# OSSI-1_LED_Controller_1.net
KiCad netlist of a schematic drawn in Altium Designer
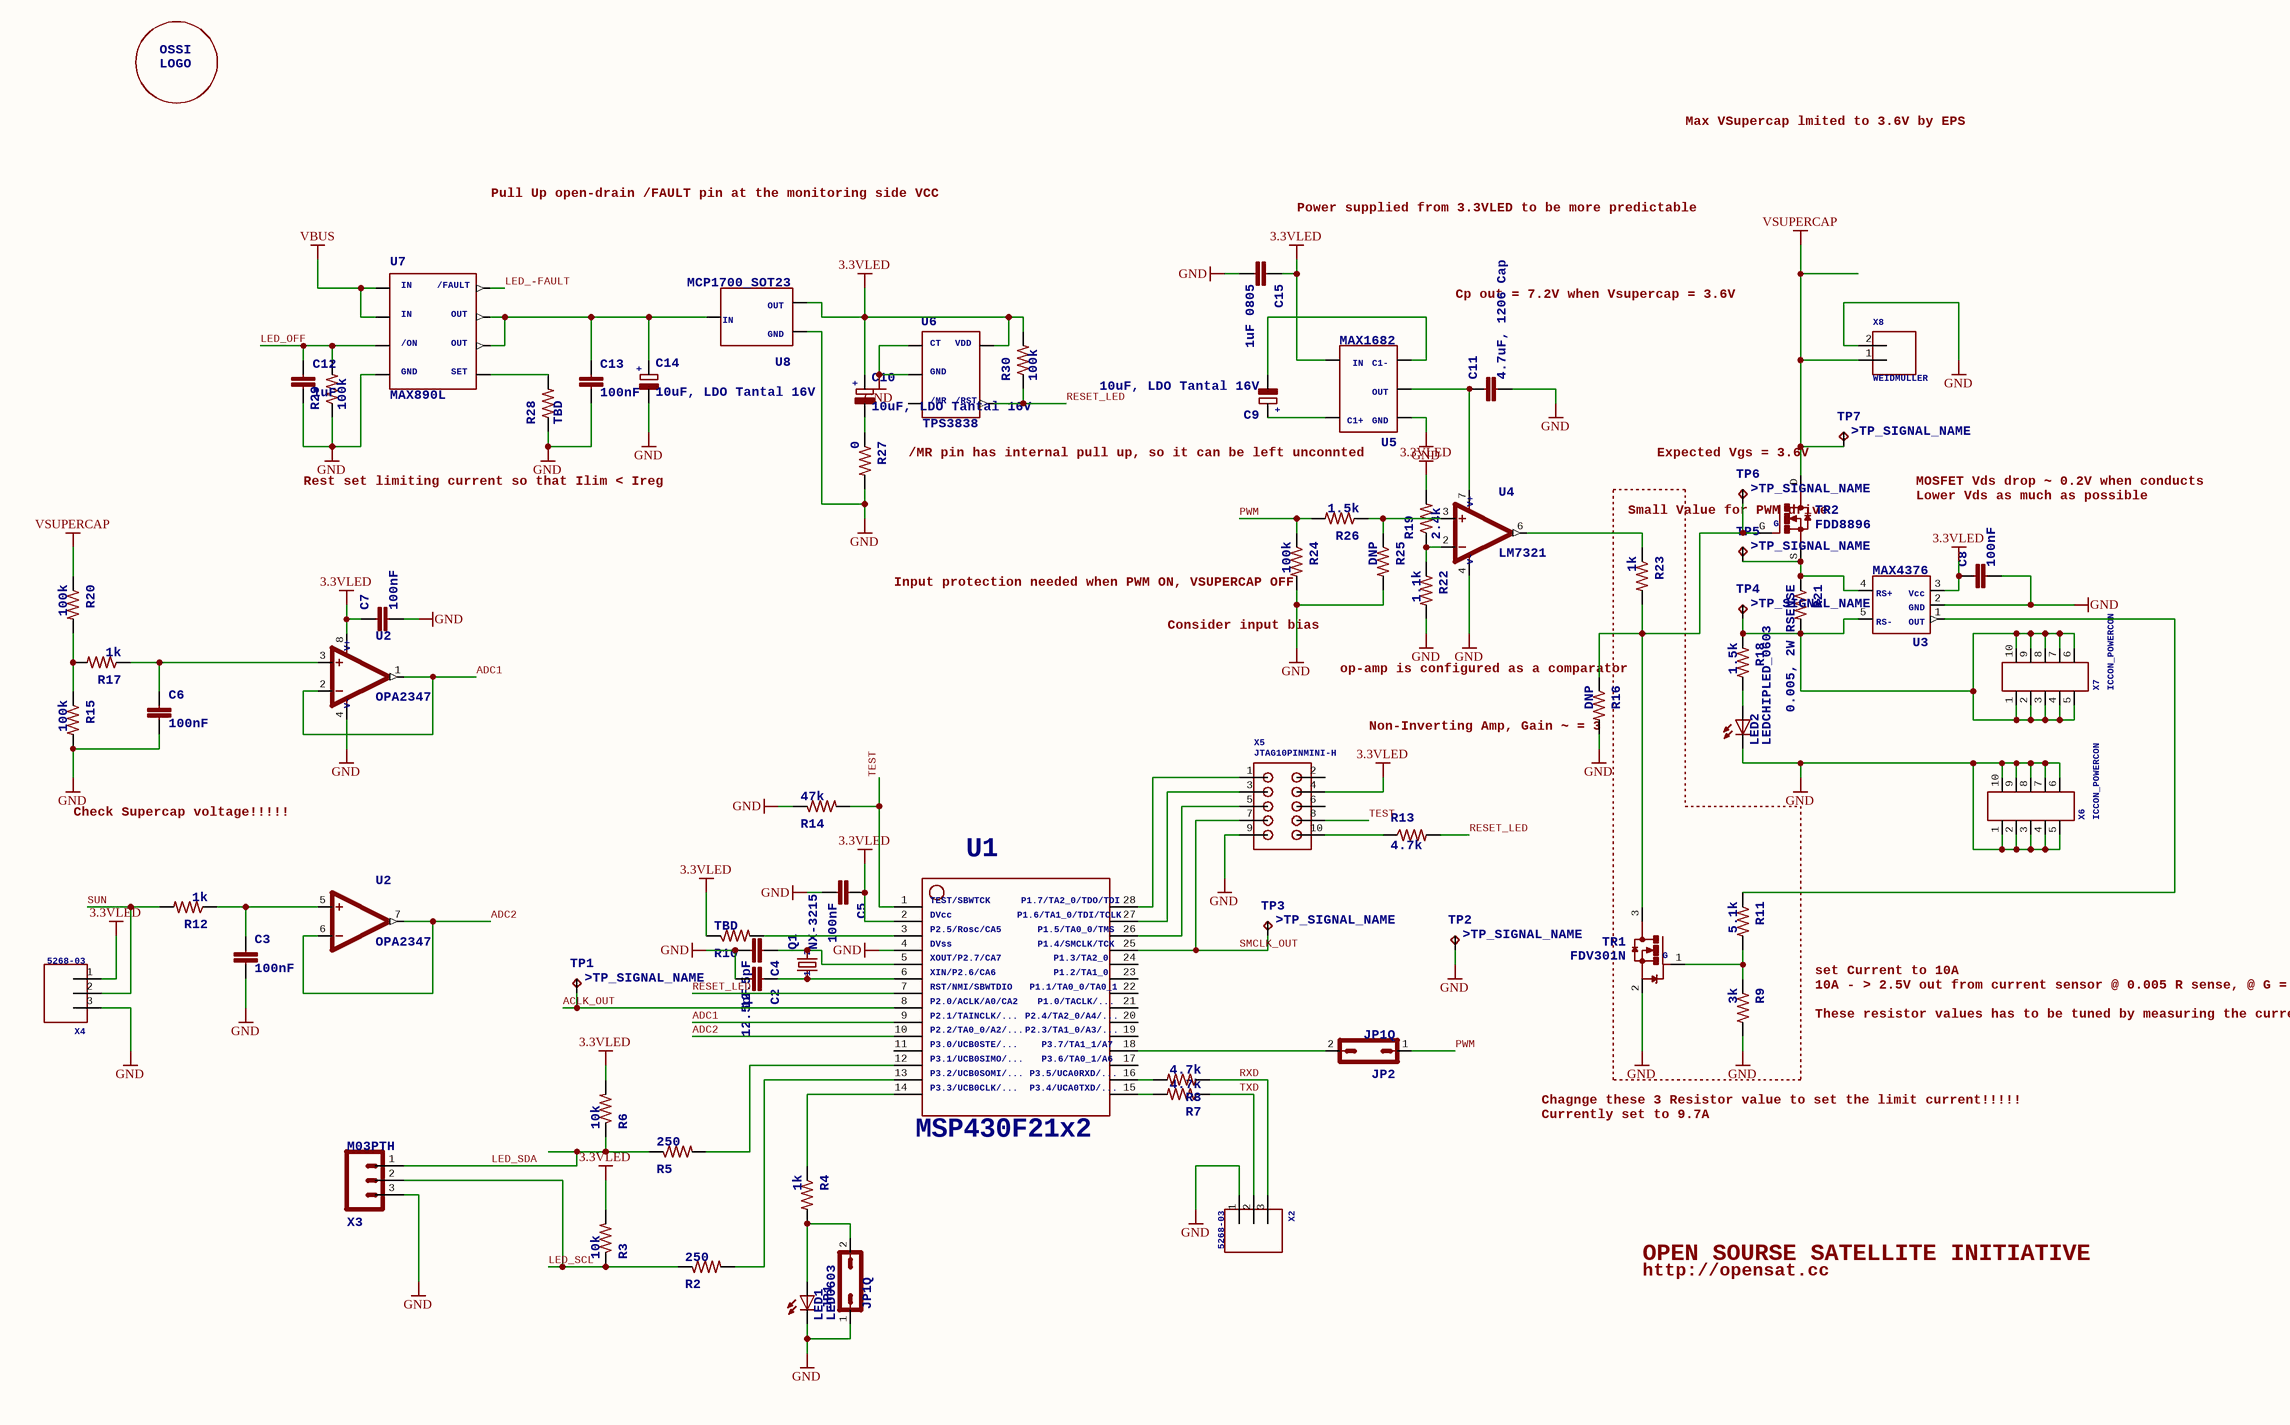
[diagram p0: OSSI-1 LED Controller_1.SchDoc]

(export (version "E")
  (design (tool "Eeschema 10.0.6"))
  (components
    (comp (ref "C2")
      (value "12.5pF")
      (footprint "C0603(1608)")
      (fields (field (name ">NAME") "C2") (field (name ">VALUE") "12.5pF"))
      (libsource (lib "") (part "C0603(1608)_2"))
    )
    (comp (ref "C3")
      (value "100nF")
      (footprint "C0603(1608)")
      (fields (field (name ">NAME") "C3") (field (name ">VALUE") "100nF"))
      (libsource (lib "OSSI") (part "C0603(1608)"))
    )
    (comp (ref "C4")
      (value "12.5pF")
      (footprint "C0603(1608)")
      (fields (field (name ">NAME") "C4") (field (name ">VALUE") "12.5pF"))
      (libsource (lib "") (part "C0603(1608)_2"))
    )
    (comp (ref "C5")
      (value "100nF")
      (footprint "C0603(1608)")
      (fields (field (name ">NAME") "C5") (field (name ">VALUE") "100nF"))
      (libsource (lib "") (part "C0603(1608)_2"))
    )
    (comp (ref "C6")
      (value "100nF")
      (footprint "C0603(1608)")
      (fields (field (name ">NAME") "C6") (field (name ">VALUE") "100nF"))
      (libsource (lib "OSSI") (part "C0603(1608)"))
    )
    (comp (ref "C7")
      (value "100nF")
      (footprint "C0603(1608)")
      (fields (field (name ">NAME") "C7") (field (name ">VALUE") "100nF"))
      (libsource (lib "") (part "C0603(1608)_1"))
    )
    (comp (ref "C8")
      (value "100nF")
      (footprint "C0603(1608)")
      (fields (field (name ">NAME") "C8") (field (name ">VALUE") "100nF"))
      (libsource (lib "") (part "C0603(1608)_1"))
    )
    (comp (ref "C9")
      (value "10uF, LDO Tantal 16V")
      (footprint "C1206(3216)-A")
      (fields
        (field (name ">NAME") "C9")
        (field (name "+") "+")
        (field (name ">VALUE") "10uF, LDO Tantal 16V")
      )
      (libsource (lib "OSSI") (part "C-TANTAL-A"))
    )
    (comp (ref "C10")
      (value "10uF, LDO Tantal 16V")
      (footprint "C1206(3216)-A")
      (fields
        (field (name ">NAME") "C10")
        (field (name "+") "+")
        (field (name ">VALUE") "10uF, LDO Tantal 16V")
      )
      (libsource (lib "") (part "C-TANTAL-A_1"))
    )
    (comp (ref "C11")
      (value "4.7uF, 1206 Cap")
      (footprint "C1206-GCM31")
      (fields (field (name ">NAME") "C11") (field (name ">VALUE") "4.7uF, 1206 Cap"))
      (libsource (lib "OSSI") (part "C1206(3216)-GCM31"))
    )
    (comp (ref "C12")
      (value "1uF")
      (footprint "C0603(1608)")
      (fields (field (name ">NAME") "C12") (field (name ">VALUE") "1uF"))
      (libsource (lib "OSSI") (part "C0603(1608)"))
    )
    (comp (ref "C13")
      (value "100nF")
      (footprint "C0603(1608)")
      (fields (field (name ">NAME") "C13") (field (name ">VALUE") "100nF"))
      (libsource (lib "OSSI") (part "C0603(1608)"))
    )
    (comp (ref "C14")
      (value "10uF, LDO Tantal 16V")
      (footprint "C1206(3216)-A")
      (fields
        (field (name ">NAME") "C14")
        (field (name "+") "+")
        (field (name ">VALUE") "10uF, LDO Tantal 16V")
      )
      (libsource (lib "") (part "C-TANTAL-A_1"))
    )
    (comp (ref "C15")
      (value "1uF 0805")
      (footprint "C0805(2012)")
      (fields (field (name ">NAME") "C15") (field (name ">VALUE") "1uF 0805"))
      (libsource (lib "OSSI") (part "C0805(2012)"))
    )
    (comp (ref "JP1")
      (value "JP1Q")
      (footprint "JP1")
      (description "<b>JUMPER</b>")
      (fields (field (name ">NAME") "JP1") (field (name ">VALUE") "JP1Q"))
      (libsource (lib "OSSI") (part "JP1Q"))
    )
    (comp (ref "JP2")
      (value "JP1Q")
      (footprint "JP1")
      (description "<b>JUMPER</b>")
      (fields (field (name ">NAME") "JP2") (field (name ">VALUE") "JP1Q"))
      (libsource (lib "OSSI") (part "JP1Q"))
    )
    (comp (ref "LED1")
      (value "LED0603")
      (footprint "LED-0603")
      (fields (field (name ">NAME") "LED1") (field (name ">VALUE") "LED0603"))
      (libsource (lib "SparkFun") (part "LED0603"))
    )
    (comp (ref "LED2")
      (value "LEDCHIPLED_0603")
      (footprint "CHIPLED_0603")
      (fields (field (name ">NAME") "LED2") (field (name ">VALUE") "LEDCHIPLED_0603"))
      (libsource (lib "led") (part "LEDCHIPLED_0603"))
    )
    (comp (ref "Q1")
      (value "NX-3215")
      (footprint "NX-3215")
      (fields
        (field (name ">NAME") "Q1")
        (field (name ">VALUE") "NX-3215")
        (field (name "1") "1")
        (field (name "2") "2")
      )
      (libsource (lib "OSSI") (part "NX-3215"))
    )
    (comp (ref "R2")
      (value "250")
      (footprint "R0603(1608)")
      (fields (field (name ">NAME") "R2") (field (name ">VALUE") "250"))
      (libsource (lib "OSSI") (part "R0603(1608)"))
    )
    (comp (ref "R3")
      (value "10k")
      (footprint "R0603(1608)")
      (fields (field (name ">NAME") "R3") (field (name ">VALUE") "10k"))
      (libsource (lib "OSSI") (part "R0603(1608)"))
    )
    (comp (ref "R4")
      (value "1k")
      (footprint "R0603(1608)")
      (fields (field (name ">NAME") "R4") (field (name ">VALUE") "1k"))
      (libsource (lib "OSSI") (part "R0603(1608)"))
    )
    (comp (ref "R5")
      (value "250")
      (footprint "R0603(1608)")
      (fields (field (name ">NAME") "R5") (field (name ">VALUE") "250"))
      (libsource (lib "OSSI") (part "R0603(1608)"))
    )
    (comp (ref "R6")
      (value "10k")
      (footprint "R0603(1608)")
      (fields (field (name ">NAME") "R6") (field (name ">VALUE") "10k"))
      (libsource (lib "OSSI") (part "R0603(1608)"))
    )
    (comp (ref "R7")
      (value "4.7k")
      (footprint "R0603(1608)")
      (fields (field (name ">NAME") "R7") (field (name ">VALUE") "4.7k"))
      (libsource (lib "OSSI") (part "R0603(1608)"))
    )
    (comp (ref "R8")
      (value "4.7k")
      (footprint "R0603(1608)")
      (fields (field (name ">NAME") "R8") (field (name ">VALUE") "4.7k"))
      (libsource (lib "OSSI") (part "R0603(1608)"))
    )
    (comp (ref "R9")
      (value "3k")
      (footprint "R0603(1608)")
      (fields (field (name ">NAME") "R9") (field (name ">VALUE") "3k"))
      (libsource (lib "OSSI") (part "R0603(1608)"))
    )
    (comp (ref "R10")
      (value "TBD")
      (footprint "R0603(1608)")
      (fields (field (name ">NAME") "R10") (field (name ">VALUE") "TBD"))
      (libsource (lib "OSSI") (part "R0603(1608)"))
    )
    (comp (ref "R11")
      (value "5.1k")
      (footprint "R0603(1608)")
      (fields (field (name ">NAME") "R11") (field (name ">VALUE") "5.1k"))
      (libsource (lib "OSSI") (part "R0603(1608)"))
    )
    (comp (ref "R12")
      (value "1k")
      (footprint "R0603(1608)")
      (fields (field (name ">NAME") "R12") (field (name ">VALUE") "1k"))
      (libsource (lib "OSSI") (part "R0603(1608)"))
    )
    (comp (ref "R13")
      (value "4.7k")
      (footprint "R0603(1608)")
      (fields (field (name ">NAME") "R13") (field (name ">VALUE") "4.7k"))
      (libsource (lib "OSSI") (part "R0603(1608)"))
    )
    (comp (ref "R14")
      (value "47k")
      (footprint "R0603(1608)")
      (fields (field (name ">NAME") "R14") (field (name ">VALUE") "47k"))
      (libsource (lib "OSSI") (part "R0603(1608)"))
    )
    (comp (ref "R15")
      (value "100k")
      (footprint "R0603(1608)")
      (fields (field (name ">NAME") "R15") (field (name ">VALUE") "100k"))
      (libsource (lib "OSSI") (part "R0603(1608)"))
    )
    (comp (ref "R16")
      (value "DNP")
      (footprint "R0603(1608)")
      (fields (field (name ">NAME") "R16") (field (name ">VALUE") "DNP"))
      (libsource (lib "OSSI") (part "R0603(1608)"))
    )
    (comp (ref "R17")
      (value "1k")
      (footprint "R0603(1608)")
      (fields (field (name ">NAME") "R17") (field (name ">VALUE") "1k"))
      (libsource (lib "OSSI") (part "R0603(1608)"))
    )
    (comp (ref "R18")
      (value "1.5k")
      (footprint "R0603(1608)")
      (fields (field (name ">NAME") "R18") (field (name ">VALUE") "1.5k"))
      (libsource (lib "OSSI") (part "R0603(1608)"))
    )
    (comp (ref "R19")
      (value "2.4k")
      (footprint "R0603(1608)")
      (fields (field (name ">NAME") "R19") (field (name ">VALUE") "2.4k"))
      (libsource (lib "OSSI") (part "R0603(1608)"))
    )
    (comp (ref "R20")
      (value "100k")
      (footprint "R0603(1608)")
      (fields (field (name ">NAME") "R20") (field (name ">VALUE") "100k"))
      (libsource (lib "OSSI") (part "R0603(1608)"))
    )
    (comp (ref "R21")
      (value "0.005, 2W RSENSE")
      (footprint "R4527(12070)")
      (fields (field (name ">NAME") "R21") (field (name ">VALUE") "0.005, 2W RSENSE"))
      (libsource (lib "OSSI") (part "RWSR2"))
    )
    (comp (ref "R22")
      (value "1.1k")
      (footprint "R0603(1608)")
      (fields (field (name ">NAME") "R22") (field (name ">VALUE") "1.1k"))
      (libsource (lib "OSSI") (part "R0603(1608)"))
    )
    (comp (ref "R23")
      (value "1k")
      (footprint "R0603(1608)")
      (fields (field (name ">NAME") "R23") (field (name ">VALUE") "1k"))
      (libsource (lib "OSSI") (part "R0603(1608)"))
    )
    (comp (ref "R24")
      (value "100k")
      (footprint "R0603(1608)")
      (fields (field (name ">NAME") "R24") (field (name ">VALUE") "100k"))
      (libsource (lib "OSSI") (part "R0603(1608)"))
    )
    (comp (ref "R25")
      (value "DNP")
      (footprint "R0603(1608)")
      (fields (field (name ">NAME") "R25") (field (name ">VALUE") "DNP"))
      (libsource (lib "OSSI") (part "R0603(1608)"))
    )
    (comp (ref "R26")
      (value "1.5k")
      (footprint "R0603(1608)")
      (fields (field (name ">NAME") "R26") (field (name ">VALUE") "1.5k"))
      (libsource (lib "OSSI") (part "R0603(1608)"))
    )
    (comp (ref "R27")
      (value "0")
      (footprint "R0603(1608)")
      (fields (field (name ">NAME") "R27") (field (name ">VALUE") "0"))
      (libsource (lib "OSSI") (part "R0603(1608)"))
    )
    (comp (ref "R28")
      (value "TBD")
      (footprint "R0603(1608)")
      (fields (field (name ">NAME") "R28") (field (name ">VALUE") "TBD"))
      (libsource (lib "OSSI") (part "R0603(1608)"))
    )
    (comp (ref "R29")
      (value "100k")
      (footprint "R0603(1608)")
      (fields (field (name ">NAME") "R29") (field (name ">VALUE") "100k"))
      (libsource (lib "OSSI") (part "R0603(1608)"))
    )
    (comp (ref "R30")
      (value "100k")
      (footprint "R0603(1608)")
      (fields (field (name ">NAME") "R30") (field (name ">VALUE") "100k"))
      (libsource (lib "OSSI") (part "R0603(1608)"))
    )
    (comp (ref "TP1")
      (value "TP")
      (footprint "TP-13")
      (fields (field (name ">NAME") "TP1") (field (name ">TP_SIGNAL_NAME") ">TP_SIGNAL_NAME"))
      (libsource (lib "OSSI") (part "TP"))
    )
    (comp (ref "TP2")
      (value "TP")
      (footprint "TP-13")
      (fields (field (name ">NAME") "TP2") (field (name ">TP_SIGNAL_NAME") ">TP_SIGNAL_NAME"))
      (libsource (lib "OSSI") (part "TP"))
    )
    (comp (ref "TP3")
      (value "TP")
      (footprint "TP-13")
      (fields (field (name ">NAME") "TP3") (field (name ">TP_SIGNAL_NAME") ">TP_SIGNAL_NAME"))
      (libsource (lib "OSSI") (part "TP"))
    )
    (comp (ref "TP4")
      (value "TP")
      (footprint "TP-13")
      (fields (field (name ">NAME") "TP4") (field (name ">TP_SIGNAL_NAME") ">TP_SIGNAL_NAME"))
      (libsource (lib "OSSI") (part "TP"))
    )
    (comp (ref "TP5")
      (value "TP")
      (footprint "TP-13")
      (fields (field (name ">NAME") "TP5") (field (name ">TP_SIGNAL_NAME") ">TP_SIGNAL_NAME"))
      (libsource (lib "OSSI") (part "TP"))
    )
    (comp (ref "TP6")
      (value "TP")
      (footprint "TP-13")
      (fields (field (name ">NAME") "TP6") (field (name ">TP_SIGNAL_NAME") ">TP_SIGNAL_NAME"))
      (libsource (lib "OSSI") (part "TP"))
    )
    (comp (ref "TP7")
      (value "TP")
      (footprint "TP-13")
      (fields (field (name ">NAME") "TP7") (field (name ">TP_SIGNAL_NAME") ">TP_SIGNAL_NAME"))
      (libsource (lib "OSSI") (part "TP"))
    )
    (comp (ref "TR1")
      (value "FDV301N")
      (footprint "SOT23")
      (description "FDV301N Digital N channel - FET / Rdson = 5 Ohm / Vgs = 0.7~1.06V / Ids = 220mA")
      (fields (field (name "G") "G") (field (name ">NAME") "TR1") (field (name ">VALUE") "FDV301N"))
      (libsource (lib "OSSI") (part "FDV301N"))
    )
    (comp (ref "TR2")
      (value "FDD8896")
      (footprint "TO252")
      (description "FDD8896<br/>\nN-Channel PowerTrench ® MOSFET")
      (fields (field (name "G") "G") (field (name ">NAME") "TR2") (field (name ">VALUE") "FDD8896"))
      (libsource (lib "OSSI") (part "FDD8896"))
    )
    (comp (ref "U$")
      (value "OSSILOGORECT")
      (footprint "OSSILOGORECT1005")
      (fields (field (name "OSSI") "OSSI") (field (name "LOGO") "LOGO"))
      (libsource (lib "OSSI") (part "OSSILOGORECT"))
    )
    (comp (ref "U1")
      (value "MSP430F2132")
      (footprint "PW28")
      (description "*** MSP430F21x2 *** PW28")
      (fields
        (field (name "TEST/SBWTCK") "TEST/SBWTCK")
        (field (name "DVCC") "DVcc")
        (field (name "P2.5/ROSC/CA5") "P2.5/Rosc/CA5")
        (field (name "DVSS") "DVss")
        (field (name "XOUT/P2.7/CA7") "XOUT/P2.7/CA7")
        (field (name "XIN/P2.6/CA6") "XIN/P2.6/CA6")
        (field (name "RST/NMI/SBWTDIO") "RST/NMI/SBWTDIO")
        (field (name "P2.0/ACLK/A0/CA2") "P2.0/ACLK/A0/CA2")
        (field (name "P2.1/TAINCLK/...") "P2.1/TAINCLK/...")
        (field (name "P2.2/TA0_0/A2/...") "P2.2/TA0_0/A2/...")
        (field (name "P1.7/TA2_0/TDO/TDI") "P1.7/TA2_0/TDO/TDI")
        (field (name "P1.6/TA1_0/TDI/TCLK") "P1.6/TA1_0/TDI/TCLK")
        (field (name "P1.5/TA0_0/TMS") "P1.5/TA0_0/TMS")
        (field (name "P1.4/SMCLK/TCK") "P1.4/SMCLK/TCK")
        (field (name "P1.3/TA2_0") "P1.3/TA2_0")
        (field (name "P1.2/TA1_0") "P1.2/TA1_0")
        (field (name "P1.1/TA0_0/TA0_1") "P1.1/TA0_0/TA0_1")
        (field (name "P1.0/TACLK/...") "P1.0/TACLK/...")
        (field (name "P2.4/TA2_0/A4/...") "P2.4/TA2_0/A4/...")
        (field (name "P2.3/TA1_0/A3/...") "P2.3/TA1_0/A3/...")
        (field (name ">NAME") "U1")
        (field (name "MSP430F21X2") "MSP430F21x2")
        (field (name "P3.7/TA1_1/A7") "P3.7/TA1_1/A7")
        (field (name "P3.6/TA0_1/A6") "P3.6/TA0_1/A6")
        (field (name "P3.5/UCA0RXD/...") "P3.5/UCA0RXD/...")
        (field (name "P3.4/UCA0TXD/...") "P3.4/UCA0TXD/...")
        (field (name "P3.3/UCB0CLK/...") "P3.3/UCB0CLK/...")
        (field (name "P3.2/UCB0SOMI/...") "P3.2/UCB0SOMI/...")
        (field (name "P3.1/UCB0SIMO/...") "P3.1/UCB0SIMO/...")
        (field (name "P3.0/UCB0STE/...") "P3.0/UCB0STE/...")
      )
      (libsource (lib "OSSI") (part "MSP430F2132"))
    )
    (comp (ref "U2")
      (value "OPA2347")
      (footprint "SOT23-8DCN")
      (fields
        (field (name ">NAME") "U2")
        (field (name ">VALUE") "OPA2347")
        (field (name "V+") "V+")
        (field (name "V-") "V-")
      )
      (libsource (lib "OSSI") (part "OPA2347"))
    )
    (comp (ref "U3")
      (value "MAX4376")
      (footprint "SOT23-5DBV")
      (fields
        (field (name ">NAME") "U3")
        (field (name ">VALUE") "MAX4376")
        (field (name "OUT") "OUT")
        (field (name "GND") "GND")
        (field (name "VCC") "Vcc")
        (field (name "RS+") "RS+")
        (field (name "RS-") "RS-")
      )
      (libsource (lib "OSSI") (part "MAX4376"))
    )
    (comp (ref "U4")
      (value "LM7321")
      (footprint "SO8")
      (fields
        (field (name ">NAME") "U4")
        (field (name ">VALUE") "LM7321")
        (field (name "V+") "V+")
        (field (name "V-") "V-")
      )
      (libsource (lib "OSSI") (part "LM7321"))
    )
    (comp (ref "U5")
      (value "MAX1682")
      (footprint "SOT23-5DBV")
      (description "MAX1682EUK+T Charge Pump")
      (fields
        (field (name ">NAME") "U5")
        (field (name ">VALUE") "MAX1682")
        (field (name "GND") "GND")
        (field (name "C1-") "C1-")
        (field (name "OUT") "OUT")
        (field (name "C1+") "C1+")
        (field (name "IN") "IN")
      )
      (libsource (lib "OSSI") (part "MAX1682"))
    )
    (comp (ref "U6")
      (value "TPS3838")
      (footprint "SOT23-5DBV")
      (fields
        (field (name ">NAME") "U6")
        (field (name ">VALUE") "TPS3838")
        (field (name "CT") "CT")
        (field (name "/MR") "/MR")
        (field (name "GND") "GND")
        (field (name "VDD") "VDD")
        (field (name "/RST") "/RST")
      )
      (libsource (lib "OSSI") (part "TPS3838"))
    )
    (comp (ref "U7")
      (value "MAX890L")
      (footprint "SO8")
      (fields
        (field (name "IN") "IN")
        (field (name "IN_1") "IN")
        (field (name "/ON") "/ON")
        (field (name "GND") "GND")
        (field (name "SET") "SET")
        (field (name "OUT") "OUT")
        (field (name "OUT_1") "OUT")
        (field (name "/FAULT") "/FAULT")
        (field (name ">NAME") "U7")
        (field (name ">VALUE") "MAX890L")
      )
      (libsource (lib "OSSI") (part "MAX890L"))
    )
    (comp (ref "U8")
      (value "MCP1700_SOT23")
      (footprint "SOT23")
      (description "MCP1700 LDO from Microchips")
      (fields
        (field (name ">NAME") "U8")
        (field (name ">VALUE") "MCP1700_SOT23")
        (field (name "IN") "IN")
        (field (name "GND") "GND")
        (field (name "OUT") "OUT")
      )
      (libsource (lib "OSSI") (part "MCP1700_SOT23"))
    )
    (comp (ref "X2")
      (value "5268-03")
      (footprint "5268-03")
      (fields (field (name ">NAME") "X2") (field (name ">VALUE") "5268-03"))
      (libsource (lib "OSSI") (part "5268-03"))
    )
    (comp (ref "X3")
      (value "M03PTH")
      (footprint "1X03")
      (fields (field (name ">VALUE") "M03PTH") (field (name ">NAME") "X3"))
      (libsource (lib "OSSI") (part "M03PTH"))
    )
    (comp (ref "X4")
      (value "5268-03")
      (footprint "5268-03")
      (fields (field (name ">NAME") "X4") (field (name ">VALUE") "5268-03"))
      (libsource (lib "OSSI") (part "5268-03"))
    )
    (comp (ref "X5")
      (value "JTAG10PINMINI-H")
      (footprint "M50-3200545")
      (fields (field (name ">NAME") "X5") (field (name ">VALUE") "JTAG10PINMINI-H"))
      (libsource (lib "OSSI") (part "JTAG10PINMINI-H"))
    )
    (comp (ref "X6")
      (value "ICCON_POWERCON")
      (footprint "ICCON6643220-1")
      (fields (field (name ">NAME") "X6") (field (name ">VALUE") "ICCON_POWERCON"))
      (libsource (lib "OSSI") (part "ICCON_POWERCON"))
    )
    (comp (ref "X7")
      (value "ICCON_POWERCON")
      (footprint "ICCON6643220-1")
      (fields (field (name ">NAME") "X7") (field (name ">VALUE") "ICCON_POWERCON"))
      (libsource (lib "OSSI") (part "ICCON_POWERCON"))
    )
    (comp (ref "X8")
      (value "WEIDMULLER")
      (footprint "WEIDMULLER1760490000")
      (fields (field (name ">NAME") "X8") (field (name ">VALUE") "WEIDMULLER"))
      (libsource (lib "OSSI") (part "WEIDMULLER"))
    )
  )
  (nets
    (net (code "1") (name "/ACLK_OUT") (class "Default")
      (node (ref "TP1") (pin "TP") (pinfunction "TP_TP") (pintype "passive"))
      (node (ref "U1") (pin "8") (pinfunction "8_8") (pintype "passive"))
    )
    (net (code "2") (name "/ADC1") (class "Default")
      (node (ref "U1") (pin "9") (pinfunction "9_9") (pintype "passive"))
      (node (ref "U2") (pin "1") (pinfunction "OUT_1") (pintype "output"))
      (node (ref "U2") (pin "2") (pinfunction "-IN_2") (pintype "passive"))
    )
    (net (code "3") (name "/ADC2") (class "Default")
      (node (ref "U1") (pin "10") (pinfunction "10_10") (pintype "passive"))
      (node (ref "U2") (pin "6") (pinfunction "-IN_6") (pintype "passive"))
      (node (ref "U2") (pin "7") (pinfunction "OUT_7") (pintype "output"))
    )
    (net (code "4") (name "/LED_-FAULT") (class "Default")
      (node (ref "U7") (pin "8") (pinfunction "P$8_8") (pintype "output"))
    )
    (net (code "5") (name "/LED_OFF") (class "Default")
      (node (ref "C12") (pin "1") (pinfunction "1_1") (pintype "passive"))
      (node (ref "R29") (pin "2") (pinfunction "2_2") (pintype "passive"))
      (node (ref "U7") (pin "3") (pinfunction "P$3_3") (pintype "passive"))
    )
    (net (code "6") (name "/LED_SCL") (class "Default")
      (node (ref "R2") (pin "1") (pinfunction "1_1") (pintype "passive"))
      (node (ref "R3") (pin "1") (pinfunction "1_1") (pintype "passive"))
      (node (ref "X3") (pin "2") (pinfunction "2_2") (pintype "passive"))
    )
    (net (code "7") (name "/LED_SDA") (class "Default")
      (node (ref "R5") (pin "1") (pinfunction "1_1") (pintype "passive"))
      (node (ref "R6") (pin "1") (pinfunction "1_1") (pintype "passive"))
      (node (ref "X3") (pin "1") (pinfunction "1_1") (pintype "passive"))
    )
    (net (code "8") (name "/PWM") (class "Default")
      (node (ref "JP2") (pin "1") (pinfunction "1_1") (pintype "passive"))
      (node (ref "R24") (pin "1") (pinfunction "1_1") (pintype "passive"))
      (node (ref "R26") (pin "2") (pinfunction "2_2") (pintype "passive"))
    )
    (net (code "9") (name "/RESET_LED") (class "Default")
      (node (ref "R13") (pin "2") (pinfunction "2_2") (pintype "passive"))
      (node (ref "R30") (pin "1") (pinfunction "1_1") (pintype "passive"))
      (node (ref "U1") (pin "7") (pinfunction "7_7") (pintype "passive"))
      (node (ref "U6") (pin "4") (pinfunction "P$4_4") (pintype "output"))
    )
    (net (code "10") (name "/RXD") (class "Default")
      (node (ref "R8") (pin "1") (pinfunction "1_1") (pintype "passive"))
      (node (ref "X2") (pin "3") (pinfunction "3_3") (pintype "passive"))
    )
    (net (code "11") (name "/SMCLK_OUT") (class "Default")
      (node (ref "TP3") (pin "TP") (pinfunction "TP_TP") (pintype "passive"))
      (node (ref "U1") (pin "25") (pinfunction "25_25") (pintype "passive"))
      (node (ref "X5") (pin "7") (pinfunction "7_7") (pintype "passive"))
    )
    (net (code "12") (name "/SUN") (class "Default")
      (node (ref "R12") (pin "2") (pinfunction "2_2") (pintype "passive"))
      (node (ref "X4") (pin "2") (pinfunction "2_2") (pintype "passive"))
    )
    (net (code "13") (name "/TEST") (class "Default")
      (node (ref "R14") (pin "2") (pinfunction "2_2") (pintype "passive"))
      (node (ref "U1") (pin "1") (pinfunction "1_1") (pintype "passive"))
      (node (ref "X5") (pin "8") (pinfunction "8_8") (pintype "passive"))
    )
    (net (code "14") (name "/TXD") (class "Default")
      (node (ref "R7") (pin "1") (pinfunction "1_1") (pintype "passive"))
      (node (ref "X2") (pin "2") (pinfunction "2_2") (pintype "passive"))
    )
    (net (code "15") (name "3.3VLED") (class "Default")
      (node (ref "C10") (pin "1") (pinfunction "+_1") (pintype "passive"))
      (node (ref "C15") (pin "1") (pinfunction "1_1") (pintype "passive"))
      (node (ref "C5") (pin "1") (pinfunction "1_1") (pintype "passive"))
      (node (ref "C7") (pin "1") (pinfunction "1_1") (pintype "passive"))
      (node (ref "C8") (pin "1") (pinfunction "1_1") (pintype "passive"))
      (node (ref "R10") (pin "1") (pinfunction "1_1") (pintype "passive"))
      (node (ref "R19") (pin "2") (pinfunction "2_2") (pintype "passive"))
      (node (ref "R3") (pin "2") (pinfunction "2_2") (pintype "passive"))
      (node (ref "R30") (pin "2") (pinfunction "2_2") (pintype "passive"))
      (node (ref "R6") (pin "2") (pinfunction "2_2") (pintype "passive"))
      (node (ref "U1") (pin "2") (pinfunction "2_2") (pintype "power_in"))
      (node (ref "U2") (pin "8") (pinfunction "V+_8") (pintype "power_in"))
      (node (ref "U3") (pin "3") (pinfunction "P$3_3") (pintype "power_in"))
      (node (ref "U5") (pin "4") (pinfunction "P$4_4") (pintype "power_in"))
      (node (ref "U6") (pin "5") (pinfunction "P$5_5") (pintype "power_in"))
      (node (ref "U8") (pin "2") (pinfunction "2_2") (pintype "power_in"))
      (node (ref "X4") (pin "1") (pinfunction "1_1") (pintype "passive"))
      (node (ref "X5") (pin "4") (pinfunction "4_4") (pintype "passive"))
    )
    (net (code "16") (name "GND") (class "Default")
      (node (ref "C11") (pin "P$2") (pinfunction "2_P$2") (pintype "passive"))
      (node (ref "C12") (pin "2") (pinfunction "2_2") (pintype "passive"))
      (node (ref "C13") (pin "2") (pinfunction "2_2") (pintype "passive"))
      (node (ref "C14") (pin "2") (pinfunction "-_2") (pintype "passive"))
      (node (ref "C15") (pin "2") (pinfunction "2_2") (pintype "passive"))
      (node (ref "C2") (pin "2") (pinfunction "2_2") (pintype "passive"))
      (node (ref "C3") (pin "2") (pinfunction "2_2") (pintype "passive"))
      (node (ref "C4") (pin "2") (pinfunction "2_2") (pintype "passive"))
      (node (ref "C5") (pin "2") (pinfunction "2_2") (pintype "passive"))
      (node (ref "C6") (pin "2") (pinfunction "2_2") (pintype "passive"))
      (node (ref "C7") (pin "2") (pinfunction "2_2") (pintype "passive"))
      (node (ref "C8") (pin "2") (pinfunction "2_2") (pintype "passive"))
      (node (ref "JP1") (pin "1") (pinfunction "1_1") (pintype "passive"))
      (node (ref "LED1") (pin "C") (pinfunction "C_C") (pintype "passive"))
      (node (ref "LED2") (pin "C") (pinfunction "C_C") (pintype "passive"))
      (node (ref "R14") (pin "1") (pinfunction "1_1") (pintype "passive"))
      (node (ref "R15") (pin "2") (pinfunction "2_2") (pintype "passive"))
      (node (ref "R16") (pin "2") (pinfunction "2_2") (pintype "passive"))
      (node (ref "R22") (pin "2") (pinfunction "2_2") (pintype "passive"))
      (node (ref "R24") (pin "2") (pinfunction "2_2") (pintype "passive"))
      (node (ref "R25") (pin "2") (pinfunction "2_2") (pintype "passive"))
      (node (ref "R27") (pin "2") (pinfunction "2_2") (pintype "passive"))
      (node (ref "R28") (pin "1") (pinfunction "1_1") (pintype "passive"))
      (node (ref "R29") (pin "1") (pinfunction "1_1") (pintype "passive"))
      (node (ref "R9") (pin "2") (pinfunction "2_2") (pintype "passive"))
      (node (ref "TP2") (pin "TP") (pinfunction "TP_TP") (pintype "passive"))
      (node (ref "TR1") (pin "2") (pinfunction "S_2") (pintype "passive"))
      (node (ref "U1") (pin "4") (pinfunction "4_4") (pintype "power_in"))
      (node (ref "U2") (pin "4") (pinfunction "V-_4") (pintype "power_in"))
      (node (ref "U3") (pin "2") (pinfunction "P$2_2") (pintype "power_in"))
      (node (ref "U4") (pin "4") (pinfunction "V-_4") (pintype "power_in"))
      (node (ref "U5") (pin "1") (pinfunction "P$1_1") (pintype "power_in"))
      (node (ref "U6") (pin "1") (pinfunction "P$1_1") (pintype "passive"))
      (node (ref "U6") (pin "2") (pinfunction "P$2_2") (pintype "power_in"))
      (node (ref "U7") (pin "4") (pinfunction "P$4_4") (pintype "power_in"))
      (node (ref "U8") (pin "1") (pinfunction "1_1") (pintype "power_in"))
      (node (ref "X2") (pin "1") (pinfunction "1_1") (pintype "passive"))
      (node (ref "X3") (pin "3") (pinfunction "3_3") (pintype "passive"))
      (node (ref "X4") (pin "3") (pinfunction "3_3") (pintype "passive"))
      (node (ref "X5") (pin "9") (pinfunction "9_9") (pintype "passive"))
      (node (ref "X6") (pin "1") (pinfunction "P$1_1") (pintype "passive"))
      (node (ref "X6") (pin "10") (pinfunction "P$10_10") (pintype "passive"))
      (node (ref "X6") (pin "2") (pinfunction "P$2_2") (pintype "passive"))
      (node (ref "X6") (pin "3") (pinfunction "P$3_3") (pintype "passive"))
      (node (ref "X6") (pin "4") (pinfunction "P$4_4") (pintype "passive"))
      (node (ref "X6") (pin "5") (pinfunction "P$5_5") (pintype "passive"))
      (node (ref "X6") (pin "6") (pinfunction "P$6_6") (pintype "passive"))
      (node (ref "X6") (pin "7") (pinfunction "P$7_7") (pintype "passive"))
      (node (ref "X6") (pin "8") (pinfunction "P$8_8") (pintype "passive"))
      (node (ref "X6") (pin "9") (pinfunction "P$9_9") (pintype "passive"))
      (node (ref "X8") (pin "2") (pinfunction "2_2") (pintype "passive"))
    )
    (net (code "17") (name "Net-(C2-Pad1)") (class "Default")
      (node (ref "C2") (pin "1") (pinfunction "1_1") (pintype "passive"))
      (node (ref "Q1") (pin "1") (pinfunction "1_1") (pintype "passive"))
      (node (ref "U1") (pin "6") (pinfunction "6_6") (pintype "passive"))
    )
    (net (code "18") (name "Net-(C4-Pad1)") (class "Default")
      (node (ref "C4") (pin "1") (pinfunction "1_1") (pintype "passive"))
      (node (ref "Q1") (pin "2") (pinfunction "2_2") (pintype "passive"))
      (node (ref "U1") (pin "5") (pinfunction "5_5") (pintype "passive"))
    )
    (net (code "19") (name "Net-(C9-+)") (class "Default")
      (node (ref "C9") (pin "1") (pinfunction "+_1") (pintype "passive"))
      (node (ref "U5") (pin "5") (pinfunction "P$5_5") (pintype "passive"))
    )
    (net (code "20") (name "Net-(C9--)") (class "Default")
      (node (ref "C9") (pin "2") (pinfunction "-_2") (pintype "passive"))
      (node (ref "U5") (pin "3") (pinfunction "P$3_3") (pintype "passive"))
    )
    (net (code "21") (name "Net-(C10--)") (class "Default")
      (node (ref "C10") (pin "2") (pinfunction "-_2") (pintype "passive"))
      (node (ref "R27") (pin "1") (pinfunction "1_1") (pintype "passive"))
    )
    (net (code "22") (name "Net-(C11-1)") (class "Default")
      (node (ref "C11") (pin "P$1") (pinfunction "1_P$1") (pintype "passive"))
      (node (ref "U4") (pin "7") (pinfunction "V+_7") (pintype "power_in"))
      (node (ref "U5") (pin "2") (pinfunction "P$2_2") (pintype "power_in"))
    )
    (net (code "23") (name "Net-(C14-+)") (class "Default")
      (node (ref "C13") (pin "1") (pinfunction "1_1") (pintype "passive"))
      (node (ref "C14") (pin "1") (pinfunction "+_1") (pintype "passive"))
      (node (ref "U7") (pin "6") (pinfunction "P$6_6") (pintype "output"))
      (node (ref "U7") (pin "7") (pinfunction "P$7_7") (pintype "output"))
      (node (ref "U8") (pin "3") (pinfunction "3_3") (pintype "power_in"))
    )
    (net (code "24") (name "Net-(JP1-Pad2)") (class "Default")
      (node (ref "JP1") (pin "2") (pinfunction "2_2") (pintype "passive"))
      (node (ref "LED1") (pin "A") (pinfunction "A_A") (pintype "passive"))
      (node (ref "R4") (pin "2") (pinfunction "2_2") (pintype "passive"))
    )
    (net (code "25") (name "Net-(JP2-Pad2)") (class "Default")
      (node (ref "JP2") (pin "2") (pinfunction "2_2") (pintype "passive"))
      (node (ref "U1") (pin "18") (pinfunction "18_18") (pintype "passive"))
    )
    (net (code "26") (name "Net-(LED2-PadA)") (class "Default")
      (node (ref "LED2") (pin "A") (pinfunction "A_A") (pintype "passive"))
      (node (ref "R18") (pin "2") (pinfunction "2_2") (pintype "passive"))
    )
    (net (code "27") (name "Net-(R2-Pad2)") (class "Default")
      (node (ref "R2") (pin "2") (pinfunction "2_2") (pintype "passive"))
      (node (ref "U1") (pin "13") (pinfunction "13_13") (pintype "passive"))
    )
    (net (code "28") (name "Net-(R4-Pad1)") (class "Default")
      (node (ref "R4") (pin "1") (pinfunction "1_1") (pintype "passive"))
      (node (ref "U1") (pin "14") (pinfunction "14_14") (pintype "passive"))
    )
    (net (code "29") (name "Net-(R5-Pad2)") (class "Default")
      (node (ref "R5") (pin "2") (pinfunction "2_2") (pintype "passive"))
      (node (ref "U1") (pin "12") (pinfunction "12_12") (pintype "passive"))
    )
    (net (code "30") (name "Net-(R7-Pad2)") (class "Default")
      (node (ref "R7") (pin "2") (pinfunction "2_2") (pintype "passive"))
      (node (ref "U1") (pin "15") (pinfunction "15_15") (pintype "passive"))
    )
    (net (code "31") (name "Net-(R8-Pad2)") (class "Default")
      (node (ref "R8") (pin "2") (pinfunction "2_2") (pintype "passive"))
      (node (ref "U1") (pin "16") (pinfunction "16_16") (pintype "passive"))
    )
    (net (code "32") (name "Net-(R10-Pad2)") (class "Default")
      (node (ref "R10") (pin "2") (pinfunction "2_2") (pintype "passive"))
      (node (ref "U1") (pin "3") (pinfunction "3_3") (pintype "passive"))
    )
    (net (code "33") (name "Net-(R13-Pad1)") (class "Default")
      (node (ref "R13") (pin "1") (pinfunction "1_1") (pintype "passive"))
      (node (ref "X5") (pin "10") (pinfunction "10_10") (pintype "passive"))
    )
    (net (code "34") (name "Net-(R15-Pad1)") (class "Default")
      (node (ref "R15") (pin "1") (pinfunction "1_1") (pintype "passive"))
      (node (ref "R17") (pin "2") (pinfunction "2_2") (pintype "passive"))
      (node (ref "R20") (pin "2") (pinfunction "2_2") (pintype "passive"))
    )
    (net (code "35") (name "Net-(R21-1)") (class "Default")
      (node (ref "R21") (pin "P$1") (pinfunction "1_P$1") (pintype "passive"))
      (node (ref "TP5") (pin "TP") (pinfunction "TP_TP") (pintype "passive"))
      (node (ref "TR2") (pin "S") (pinfunction "S_S") (pintype "passive"))
      (node (ref "U3") (pin "4") (pinfunction "P$4_4") (pintype "passive"))
    )
    (net (code "36") (name "Net-(R21-2)") (class "Default")
      (node (ref "R18") (pin "1") (pinfunction "1_1") (pintype "passive"))
      (node (ref "R21") (pin "P$2") (pinfunction "2_P$2") (pintype "passive"))
      (node (ref "TP4") (pin "TP") (pinfunction "TP_TP") (pintype "passive"))
      (node (ref "U3") (pin "5") (pinfunction "P$5_5") (pintype "passive"))
      (node (ref "X7") (pin "1") (pinfunction "P$1_1") (pintype "passive"))
      (node (ref "X7") (pin "10") (pinfunction "P$10_10") (pintype "passive"))
      (node (ref "X7") (pin "2") (pinfunction "P$2_2") (pintype "passive"))
      (node (ref "X7") (pin "3") (pinfunction "P$3_3") (pintype "passive"))
      (node (ref "X7") (pin "4") (pinfunction "P$4_4") (pintype "passive"))
      (node (ref "X7") (pin "5") (pinfunction "P$5_5") (pintype "passive"))
      (node (ref "X7") (pin "6") (pinfunction "P$6_6") (pintype "passive"))
      (node (ref "X7") (pin "7") (pinfunction "P$7_7") (pintype "passive"))
      (node (ref "X7") (pin "8") (pinfunction "P$8_8") (pintype "passive"))
      (node (ref "X7") (pin "9") (pinfunction "P$9_9") (pintype "passive"))
    )
    (net (code "37") (name "Net-(TR1-D)") (class "Default")
      (node (ref "R16") (pin "1") (pinfunction "1_1") (pintype "passive"))
      (node (ref "R23") (pin "2") (pinfunction "2_2") (pintype "passive"))
      (node (ref "TP6") (pin "TP") (pinfunction "TP_TP") (pintype "passive"))
      (node (ref "TR1") (pin "3") (pinfunction "D_3") (pintype "passive"))
      (node (ref "TR2") (pin "G") (pinfunction "G_G") (pintype "passive"))
    )
    (net (code "38") (name "Net-(TR1-G)") (class "Default")
      (node (ref "R11") (pin "2") (pinfunction "2_2") (pintype "passive"))
      (node (ref "R9") (pin "1") (pinfunction "1_1") (pintype "passive"))
      (node (ref "TR1") (pin "1") (pinfunction "G_1") (pintype "passive"))
    )
    (net (code "39") (name "Net-(U1-Pad26)") (class "Default")
      (node (ref "U1") (pin "26") (pinfunction "26_26") (pintype "passive"))
      (node (ref "X5") (pin "5") (pinfunction "5_5") (pintype "passive"))
    )
    (net (code "40") (name "Net-(U1-Pad27)") (class "Default")
      (node (ref "U1") (pin "27") (pinfunction "27_27") (pintype "passive"))
      (node (ref "X5") (pin "3") (pinfunction "3_3") (pintype "passive"))
    )
    (net (code "41") (name "Net-(U1-Pad28)") (class "Default")
      (node (ref "U1") (pin "28") (pinfunction "28_28") (pintype "passive"))
      (node (ref "X5") (pin "1") (pinfunction "1_1") (pintype "passive"))
    )
    (net (code "42") (name "Net-(U2A-+IN)") (class "Default")
      (node (ref "C6") (pin "1") (pinfunction "1_1") (pintype "passive"))
      (node (ref "R17") (pin "1") (pinfunction "1_1") (pintype "passive"))
      (node (ref "U2") (pin "3") (pinfunction "+IN_3") (pintype "passive"))
    )
    (net (code "43") (name "Net-(U2B-+IN)") (class "Default")
      (node (ref "C3") (pin "1") (pinfunction "1_1") (pintype "passive"))
      (node (ref "R12") (pin "1") (pinfunction "1_1") (pintype "passive"))
      (node (ref "U2") (pin "5") (pinfunction "+IN_5") (pintype "passive"))
    )
    (net (code "44") (name "Net-(U3-P$1)") (class "Default")
      (node (ref "R11") (pin "1") (pinfunction "1_1") (pintype "passive"))
      (node (ref "U3") (pin "1") (pinfunction "P$1_1") (pintype "output"))
    )
    (net (code "45") (name "Net-(U4-+IN)") (class "Default")
      (node (ref "R25") (pin "1") (pinfunction "1_1") (pintype "passive"))
      (node (ref "R26") (pin "1") (pinfunction "1_1") (pintype "passive"))
      (node (ref "U4") (pin "3") (pinfunction "+IN_3") (pintype "passive"))
    )
    (net (code "46") (name "Net-(U4--IN)") (class "Default")
      (node (ref "R19") (pin "1") (pinfunction "1_1") (pintype "passive"))
      (node (ref "R22") (pin "1") (pinfunction "1_1") (pintype "passive"))
      (node (ref "U4") (pin "2") (pinfunction "-IN_2") (pintype "passive"))
    )
    (net (code "47") (name "Net-(U4-OUT)") (class "Default")
      (node (ref "R23") (pin "1") (pinfunction "1_1") (pintype "passive"))
      (node (ref "U4") (pin "6") (pinfunction "OUT_6") (pintype "output"))
    )
    (net (code "48") (name "Net-(U7-P$5)") (class "Default")
      (node (ref "R28") (pin "2") (pinfunction "2_2") (pintype "passive"))
      (node (ref "U7") (pin "5") (pinfunction "P$5_5") (pintype "passive"))
    )
    (net (code "49") (name "VBUS") (class "Default")
      (node (ref "U7") (pin "1") (pinfunction "P$1_1") (pintype "passive"))
      (node (ref "U7") (pin "2") (pinfunction "P$2_2") (pintype "passive"))
    )
    (net (code "50") (name "VSUPERCAP") (class "Default")
      (node (ref "R20") (pin "1") (pinfunction "1_1") (pintype "passive"))
      (node (ref "TP7") (pin "TP") (pinfunction "TP_TP") (pintype "passive"))
      (node (ref "TR2") (pin "D") (pinfunction "D_D") (pintype "passive"))
      (node (ref "X8") (pin "1") (pinfunction "1_1") (pintype "passive"))
    )
    (net (code "51") (name "unconnected-(U1-Pad11)") (class "Default")
      (node (ref "U1") (pin "11") (pinfunction "11_11") (pintype "passive"))
    )
    (net (code "52") (name "unconnected-(U1-Pad17)") (class "Default")
      (node (ref "U1") (pin "17") (pinfunction "17_17") (pintype "passive"))
    )
    (net (code "53") (name "unconnected-(U1-Pad19)") (class "Default")
      (node (ref "U1") (pin "19") (pinfunction "19_19") (pintype "passive"))
    )
    (net (code "54") (name "unconnected-(U1-Pad20)") (class "Default")
      (node (ref "U1") (pin "20") (pinfunction "20_20") (pintype "passive"))
    )
    (net (code "55") (name "unconnected-(U1-Pad21)") (class "Default")
      (node (ref "U1") (pin "21") (pinfunction "21_21") (pintype "passive"))
    )
    (net (code "56") (name "unconnected-(U1-Pad22)") (class "Default")
      (node (ref "U1") (pin "22") (pinfunction "22_22") (pintype "passive"))
    )
    (net (code "57") (name "unconnected-(U1-Pad23)") (class "Default")
      (node (ref "U1") (pin "23") (pinfunction "23_23") (pintype "passive"))
    )
    (net (code "58") (name "unconnected-(U1-Pad24)") (class "Default")
      (node (ref "U1") (pin "24") (pinfunction "24_24") (pintype "passive"))
    )
    (net (code "59") (name "unconnected-(U6-P$3-Pad3)") (class "Default")
      (node (ref "U6") (pin "3") (pinfunction "P$3_3") (pintype "passive"))
    )
    (net (code "60") (name "unconnected-(X5-Pad2)") (class "Default")
      (node (ref "X5") (pin "2") (pinfunction "2_2") (pintype "passive"))
    )
    (net (code "61") (name "unconnected-(X5-Pad6)") (class "Default")
      (node (ref "X5") (pin "6") (pinfunction "6_6") (pintype "passive"))
    )
  )
)
